# Sheet2.net
KiCad netlist of a schematic drawn in Altium Designer
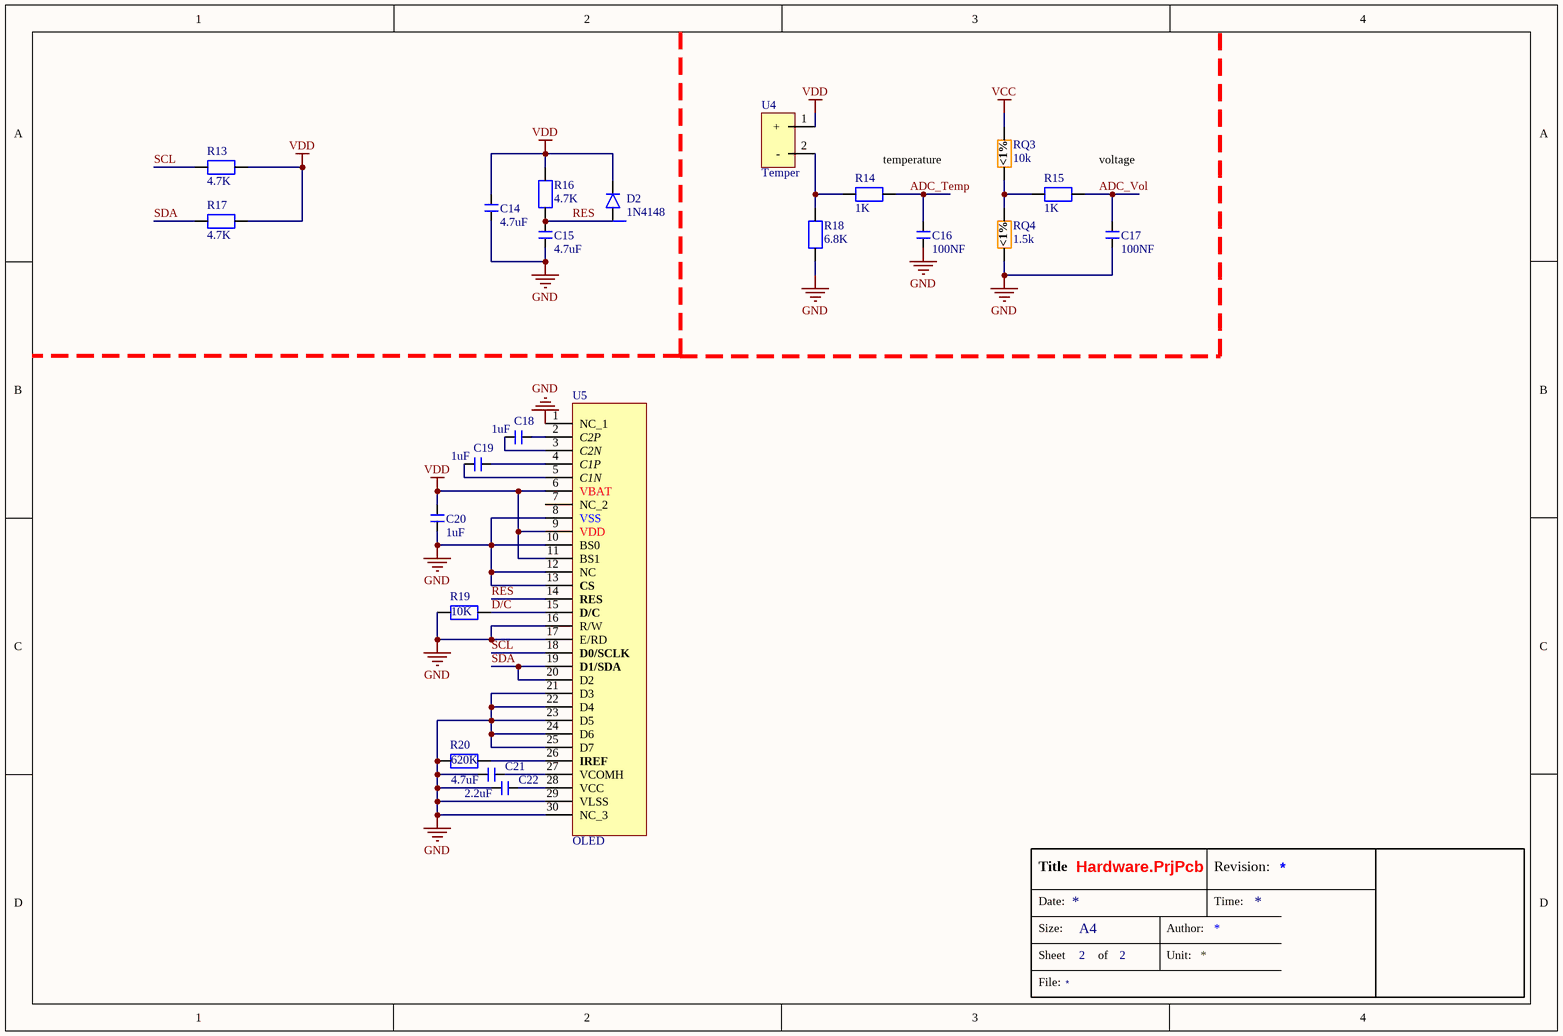
[diagram p0: Sheet2.SchDoc]

(export (version "E")
  (design (tool "Eeschema 10.0.6"))
  (components
    (comp (ref "C14")
      (value "4.7uF")
      (footprint "CAP_0603")
      (description "CAP  12~50V")
      (libsource (lib "User") (part "CAP"))
    )
    (comp (ref "C15")
      (value "4.7uF")
      (footprint "CAP_0603")
      (description "CAP  12~50V")
      (libsource (lib "User") (part "CAP"))
    )
    (comp (ref "C16")
      (value "100NF")
      (footprint "CAP_0603")
      (description "CAP  12~50V")
      (libsource (lib "User") (part "CAP"))
    )
    (comp (ref "C17")
      (value "100NF")
      (footprint "CAP_0603")
      (description "CAP  12~50V")
      (libsource (lib "User") (part "CAP"))
    )
    (comp (ref "C18")
      (value "1uF")
      (footprint "CAP_0603")
      (description "CAP  12~50V")
      (libsource (lib "User") (part "CAP"))
    )
    (comp (ref "C19")
      (value "1uF")
      (footprint "CAP_0603")
      (description "CAP  12~50V")
      (libsource (lib "User") (part "CAP"))
    )
    (comp (ref "C20")
      (value "1uF")
      (footprint "CAP_0603")
      (description "CAP  12~50V")
      (libsource (lib "User") (part "CAP"))
    )
    (comp (ref "C21")
      (value "4.7uF")
      (footprint "CAP_0603")
      (description "CAP  12~50V")
      (libsource (lib "User") (part "CAP"))
    )
    (comp (ref "C22")
      (value "2.2uF")
      (footprint "CAP_0603")
      (description "CAP  12~50V")
      (libsource (lib "User") (part "CAP"))
    )
    (comp (ref "D2")
      (value "1N4148")
      (footprint "DIODE_SOD123")
      (description "Diode_肖特基/二极管")
      (libsource (lib "User") (part "Diode-SM"))
    )
    (comp (ref "R13")
      (value "4.7K")
      (footprint "RESC_0603_2")
      (description "RES 贴片")
      (libsource (lib "User") (part "RES"))
    )
    (comp (ref "R14")
      (value "1K")
      (footprint "RESC_0603_2")
      (description "RES 贴片")
      (libsource (lib "User") (part "RES"))
    )
    (comp (ref "R15")
      (value "1K")
      (footprint "RESC_0603_2")
      (description "RES 贴片")
      (libsource (lib "User") (part "RES"))
    )
    (comp (ref "R16")
      (value "4.7K")
      (footprint "RESC_0603_2")
      (description "RES 贴片")
      (libsource (lib "User") (part "RES"))
    )
    (comp (ref "R17")
      (value "4.7K")
      (footprint "RESC_0603_2")
      (description "RES 贴片")
      (libsource (lib "User") (part "RES"))
    )
    (comp (ref "R18")
      (value "6.8K")
      (footprint "RESC_0603_2")
      (description "RES 贴片")
      (libsource (lib "User") (part "RES"))
    )
    (comp (ref "R19")
      (value "10K")
      (footprint "RESC_0603_2")
      (description "RES 贴片")
      (libsource (lib "User") (part "RES"))
    )
    (comp (ref "R20")
      (value "620K")
      (footprint "RESC_0603_2")
      (description "RES 贴片")
      (libsource (lib "User") (part "RES"))
    )
    (comp (ref "RQ3")
      (value "10k")
      (footprint "RESC_0603_2")
      (description "RES")
      (libsource (lib "User") (part "RES_quality"))
    )
    (comp (ref "RQ4")
      (value "1.5k")
      (footprint "RESC_0603_2")
      (description "RES")
      (libsource (lib "User") (part "RES_quality"))
    )
    (comp (ref "U4")
      (value "Temper")
      (footprint "RESC_0603_1")
      (description "Mode")
      (libsource (lib "User") (part "Temper"))
    )
    (comp (ref "U5")
      (value "OLED")
      (footprint "OLED_0.96")
      (description "SHOW")
      (libsource (lib "User") (part "OLED_0.96"))
    )
  )
  (nets
    (net (code "1") (name "/ADC_Temp") (class "Default")
      (node (ref "C16") (pin "2") (pinfunction "0_2") (pintype "passive"))
      (node (ref "R14") (pin "2") (pinfunction "2_2") (pintype "passive"))
    )
    (net (code "2") (name "/ADC_Vol") (class "Default")
      (node (ref "C17") (pin "2") (pinfunction "0_2") (pintype "passive"))
      (node (ref "R15") (pin "2") (pinfunction "2_2") (pintype "passive"))
    )
    (net (code "3") (name "/D{slash}C") (class "Default")
      (node (ref "R19") (pin "1") (pinfunction "1_1") (pintype "passive"))
      (node (ref "U5") (pin "15") (pinfunction "D/C_15") (pintype "passive"))
    )
    (net (code "4") (name "/RES") (class "Default")
      (node (ref "C15") (pin "2") (pinfunction "0_2") (pintype "passive"))
      (node (ref "D2") (pin "1") (pinfunction "P_1") (pintype "passive"))
      (node (ref "R16") (pin "1") (pinfunction "1_1") (pintype "passive"))
      (node (ref "U5") (pin "14") (pinfunction "RES_14") (pintype "passive"))
    )
    (net (code "5") (name "/SCL") (class "Default")
      (node (ref "R13") (pin "2") (pinfunction "2_2") (pintype "passive"))
      (node (ref "U5") (pin "18") (pinfunction "D0/SCLK_18") (pintype "passive"))
    )
    (net (code "6") (name "/SDA") (class "Default")
      (node (ref "R17") (pin "2") (pinfunction "2_2") (pintype "passive"))
      (node (ref "U5") (pin "19") (pinfunction "D1/SDA_19") (pintype "passive"))
      (node (ref "U5") (pin "20") (pinfunction "D2_20") (pintype "passive"))
    )
    (net (code "7") (name "GND") (class "Default")
      (node (ref "C14") (pin "1") (pinfunction "0_1") (pintype "passive"))
      (node (ref "C15") (pin "1") (pinfunction "0_1") (pintype "passive"))
      (node (ref "C16") (pin "1") (pinfunction "0_1") (pintype "passive"))
      (node (ref "C17") (pin "1") (pinfunction "0_1") (pintype "passive"))
      (node (ref "C20") (pin "2") (pinfunction "0_2") (pintype "passive"))
      (node (ref "C21") (pin "2") (pinfunction "0_2") (pintype "passive"))
      (node (ref "C22") (pin "2") (pinfunction "0_2") (pintype "passive"))
      (node (ref "R18") (pin "2") (pinfunction "2_2") (pintype "passive"))
      (node (ref "R19") (pin "2") (pinfunction "2_2") (pintype "passive"))
      (node (ref "R20") (pin "2") (pinfunction "2_2") (pintype "passive"))
      (node (ref "RQ4") (pin "1") (pinfunction "1_1") (pintype "passive"))
      (node (ref "U5") (pin "1") (pinfunction "NC_1_1") (pintype "passive"))
      (node (ref "U5") (pin "10") (pinfunction "BS0_10") (pintype "passive"))
      (node (ref "U5") (pin "12") (pinfunction "NC_12") (pintype "passive"))
      (node (ref "U5") (pin "13") (pinfunction "CS_13") (pintype "passive"))
      (node (ref "U5") (pin "16") (pinfunction "R/W_16") (pintype "passive"))
      (node (ref "U5") (pin "17") (pinfunction "E/RD_17") (pintype "passive"))
      (node (ref "U5") (pin "21") (pinfunction "D3_21") (pintype "passive"))
      (node (ref "U5") (pin "22") (pinfunction "D4_22") (pintype "passive"))
      (node (ref "U5") (pin "23") (pinfunction "D5_23") (pintype "passive"))
      (node (ref "U5") (pin "24") (pinfunction "D6_24") (pintype "passive"))
      (node (ref "U5") (pin "25") (pinfunction "D7_25") (pintype "passive"))
      (node (ref "U5") (pin "29") (pinfunction "VLSS_29") (pintype "passive"))
      (node (ref "U5") (pin "30") (pinfunction "NC_3_30") (pintype "passive"))
      (node (ref "U5") (pin "8") (pinfunction "VSS_8") (pintype "passive"))
    )
    (net (code "8") (name "Net-(R15-Pad1)") (class "Default")
      (node (ref "R15") (pin "1") (pinfunction "1_1") (pintype "passive"))
      (node (ref "RQ3") (pin "1") (pinfunction "1_1") (pintype "passive"))
      (node (ref "RQ4") (pin "2") (pinfunction "2_2") (pintype "passive"))
    )
    (net (code "9") (name "Net-(U4--)") (class "Default")
      (node (ref "R14") (pin "1") (pinfunction "1_1") (pintype "passive"))
      (node (ref "R18") (pin "1") (pinfunction "1_1") (pintype "passive"))
      (node (ref "U4") (pin "2") (pinfunction "-_2") (pintype "passive"))
    )
    (net (code "10") (name "Net-(U5-C1N)") (class "Default")
      (node (ref "C19") (pin "2") (pinfunction "0_2") (pintype "passive"))
      (node (ref "U5") (pin "5") (pinfunction "C1N_5") (pintype "passive"))
    )
    (net (code "11") (name "Net-(U5-C1P)") (class "Default")
      (node (ref "C19") (pin "1") (pinfunction "0_1") (pintype "passive"))
      (node (ref "U5") (pin "4") (pinfunction "C1P_4") (pintype "passive"))
    )
    (net (code "12") (name "Net-(U5-C2N)") (class "Default")
      (node (ref "C18") (pin "2") (pinfunction "0_2") (pintype "passive"))
      (node (ref "U5") (pin "3") (pinfunction "C2N_3") (pintype "passive"))
    )
    (net (code "13") (name "Net-(U5-C2P)") (class "Default")
      (node (ref "C18") (pin "1") (pinfunction "0_1") (pintype "passive"))
      (node (ref "U5") (pin "2") (pinfunction "C2P_2") (pintype "passive"))
    )
    (net (code "14") (name "Net-(U5-IREF)") (class "Default")
      (node (ref "R20") (pin "1") (pinfunction "1_1") (pintype "passive"))
      (node (ref "U5") (pin "26") (pinfunction "IREF_26") (pintype "passive"))
    )
    (net (code "15") (name "Net-(U5-VCC)") (class "Default")
      (node (ref "C22") (pin "1") (pinfunction "0_1") (pintype "passive"))
      (node (ref "U5") (pin "28") (pinfunction "VCC_28") (pintype "passive"))
    )
    (net (code "16") (name "Net-(U5-VCOMH)") (class "Default")
      (node (ref "C21") (pin "1") (pinfunction "0_1") (pintype "passive"))
      (node (ref "U5") (pin "27") (pinfunction "VCOMH_27") (pintype "passive"))
    )
    (net (code "17") (name "VCC") (class "Default")
      (node (ref "RQ3") (pin "2") (pinfunction "2_2") (pintype "passive"))
    )
    (net (code "18") (name "VDD") (class "Default")
      (node (ref "C14") (pin "2") (pinfunction "0_2") (pintype "passive"))
      (node (ref "C20") (pin "1") (pinfunction "0_1") (pintype "passive"))
      (node (ref "D2") (pin "2") (pinfunction "N_2") (pintype "passive"))
      (node (ref "R13") (pin "1") (pinfunction "1_1") (pintype "passive"))
      (node (ref "R16") (pin "2") (pinfunction "2_2") (pintype "passive"))
      (node (ref "R17") (pin "1") (pinfunction "1_1") (pintype "passive"))
      (node (ref "U4") (pin "1") (pinfunction "+_1") (pintype "passive"))
      (node (ref "U5") (pin "11") (pinfunction "BS1_11") (pintype "passive"))
      (node (ref "U5") (pin "6") (pinfunction "VBAT_6") (pintype "passive"))
      (node (ref "U5") (pin "9") (pinfunction "VDD_9") (pintype "passive"))
    )
    (net (code "19") (name "unconnected-(U5-NC_2-Pad7)") (class "Default")
      (node (ref "U5") (pin "7") (pinfunction "NC_2_7") (pintype "passive"))
    )
  )
)
